# tlc5940_tranzisztor.net
KiCad netlist of a schematic drawn in EAGLE
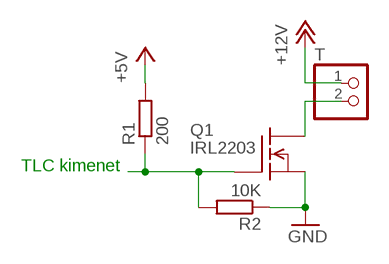
[diagram p0: schematic, sheet 1]

(export (version "E")
  (design (tool "Eeschema 10.0.6"))
  (components
    (comp (ref "Q1")
      (value "IRL2203")
      (footprint "eagle-import:TO220")
      (libsource (lib "eagle-import") (part "BUZ10"))
    )
    (comp (ref "R1")
      (value "200")
      (footprint "eagle-import:0207_10")
      (libsource (lib "eagle-import") (part "R-EU_0207/10"))
    )
    (comp (ref "R2")
      (value "10K")
      (footprint "eagle-import:0207_10")
      (libsource (lib "eagle-import") (part "R-EU_0207/10"))
    )
    (comp (ref "T")
      (value "PINHD-1X2")
      (footprint "eagle-import:1X02")
      (libsource (lib "eagle-import") (part "PINHD-1X2"))
    )
  )
  (nets
    (net (code "1") (name "+5V") (class "Default")
      (node (ref "R1") (pin "2") (pinfunction "2_2") (pintype "passive"))
    )
    (net (code "2") (name "+12V") (class "Default")
      (node (ref "T") (pin "1") (pinfunction "1_1") (pintype "passive"))
    )
    (net (code "3") (name "GND") (class "Default")
      (node (ref "Q1") (pin "3") (pinfunction "S_3") (pintype "passive"))
      (node (ref "R2") (pin "1") (pinfunction "1_1") (pintype "passive"))
    )
    (net (code "4") (name "Net-(Q1-D)") (class "Default")
      (node (ref "Q1") (pin "2") (pinfunction "D_2") (pintype "passive"))
      (node (ref "T") (pin "2") (pinfunction "2_2") (pintype "passive"))
    )
    (net (code "5") (name "Net-(Q1-G)") (class "Default")
      (node (ref "Q1") (pin "1") (pinfunction "G_1") (pintype "passive"))
      (node (ref "R1") (pin "1") (pinfunction "1_1") (pintype "passive"))
      (node (ref "R2") (pin "2") (pinfunction "2_2") (pintype "passive"))
    )
  )
)
